# crowlar.net
KiCad netlist of a schematic drawn in EAGLE
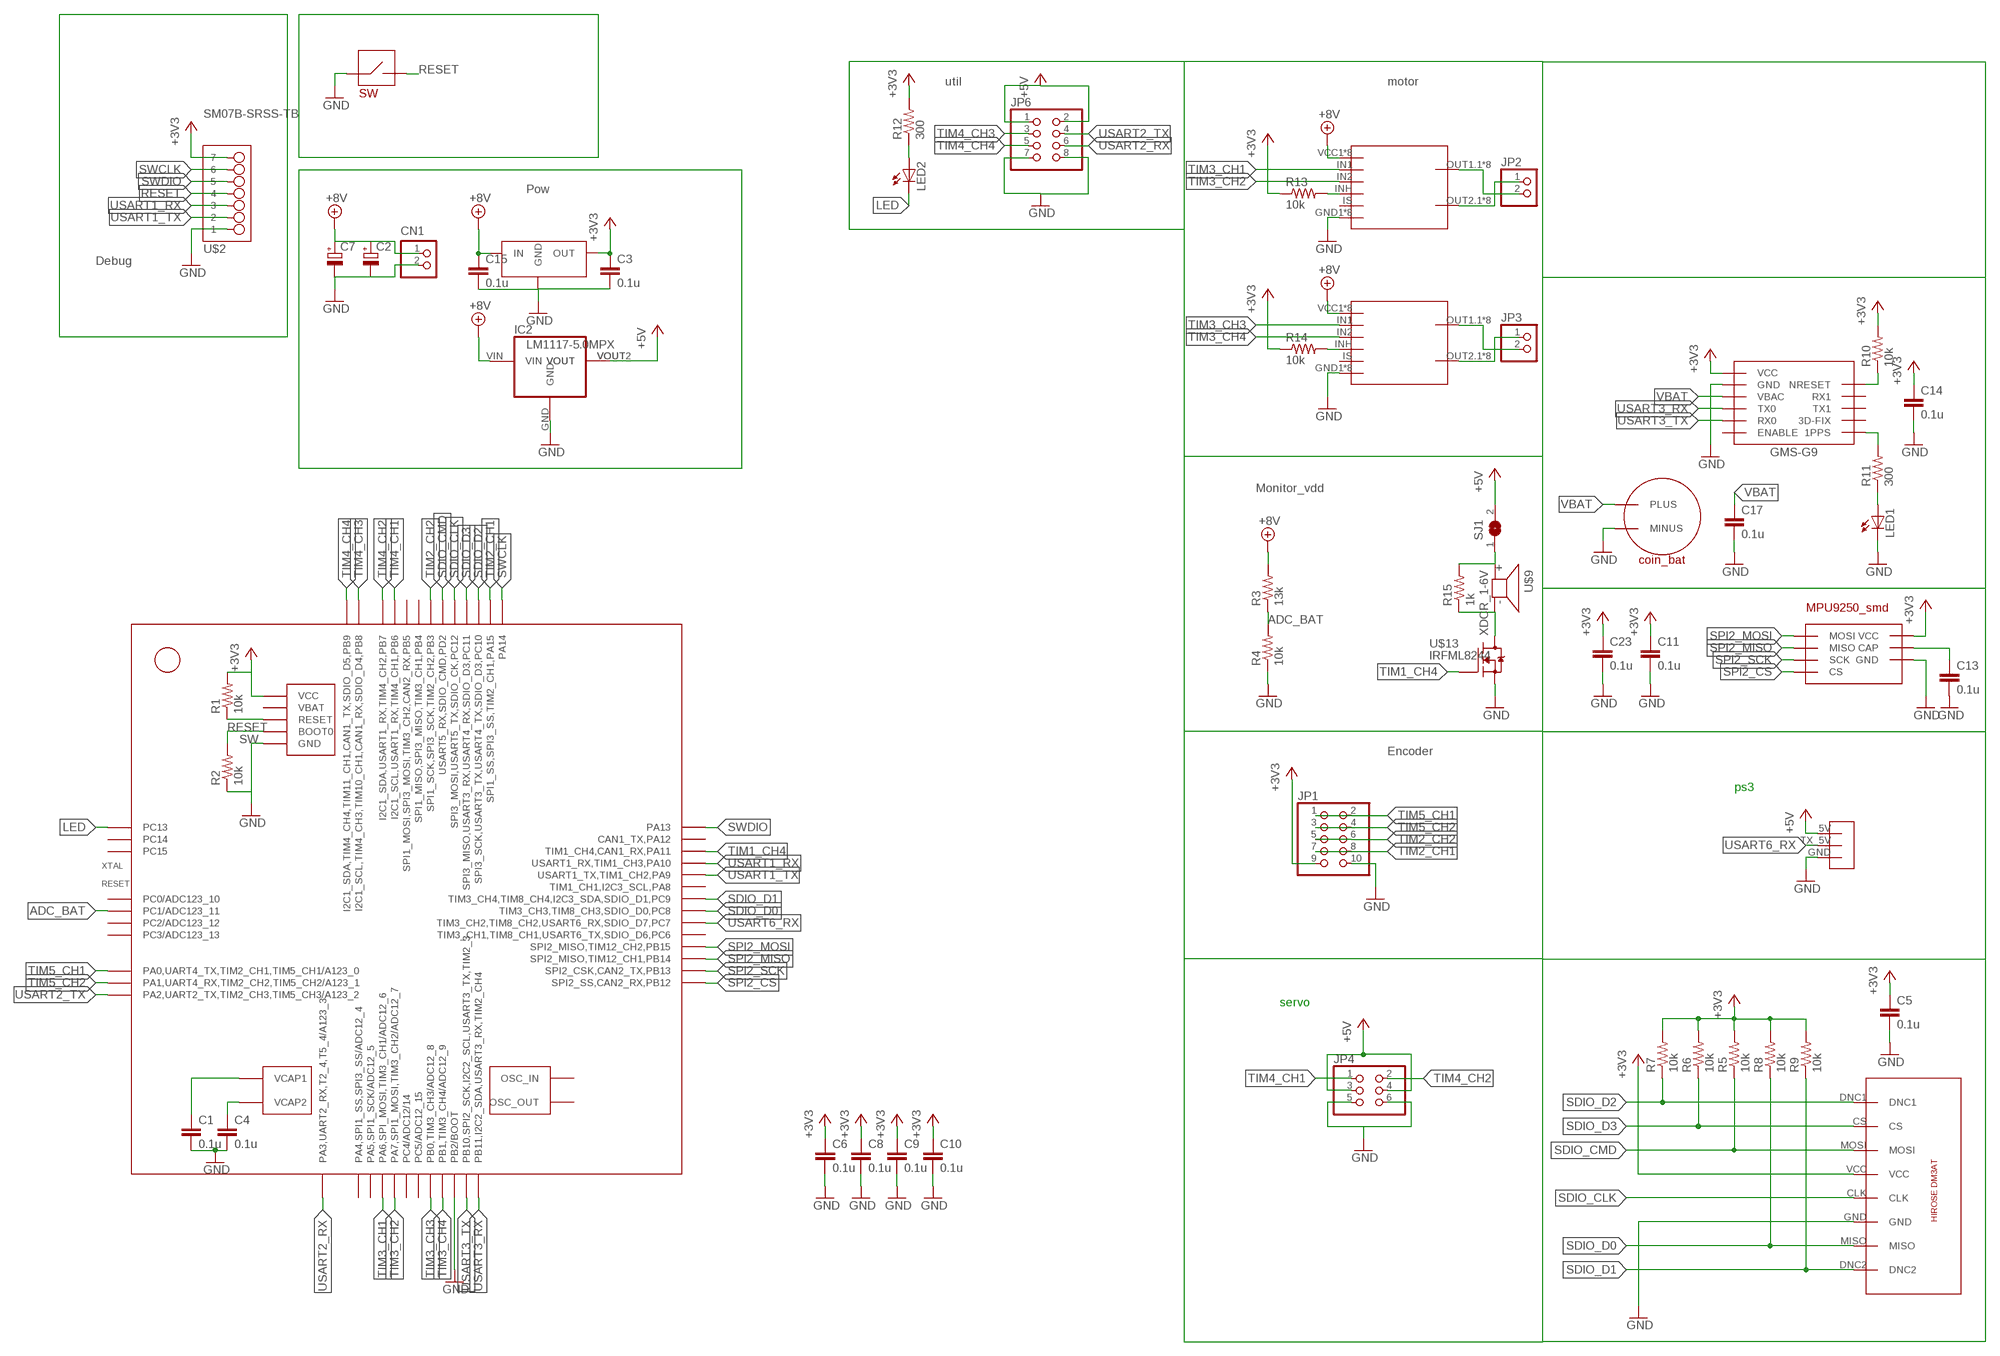
[diagram p0: schematic, sheet 1]

(export (version "E")
  (design (tool "Eeschema 10.0.6"))
  (components
    (comp (ref "C1")
      (value "0.1u")
      (footprint "eagle-import:C0603K")
      (libsource (lib "eagle-import") (part "C-EUC0603K"))
    )
    (comp (ref "C2")
      (value "CPOL-EU153CLV-0605")
      (footprint "eagle-import:153CLV-0605")
      (libsource (lib "eagle-import") (part "CPOL-EU153CLV-0605"))
    )
    (comp (ref "C3")
      (value "0.1u")
      (footprint "eagle-import:C0603K")
      (libsource (lib "eagle-import") (part "C-EUC0603K"))
    )
    (comp (ref "C4")
      (value "0.1u")
      (footprint "eagle-import:C0603K")
      (libsource (lib "eagle-import") (part "C-EUC0603K"))
    )
    (comp (ref "C5")
      (value "0.1u")
      (footprint "eagle-import:C0603K")
      (libsource (lib "eagle-import") (part "C-EUC0603K"))
    )
    (comp (ref "C6")
      (value "0.1u")
      (footprint "eagle-import:C0603K")
      (libsource (lib "eagle-import") (part "C-EUC0603K"))
    )
    (comp (ref "C7")
      (value "CPOL-EU153CLV-0605")
      (footprint "eagle-import:153CLV-0605")
      (libsource (lib "eagle-import") (part "CPOL-EU153CLV-0605"))
    )
    (comp (ref "C8")
      (value "0.1u")
      (footprint "eagle-import:C0603K")
      (libsource (lib "eagle-import") (part "C-EUC0603K"))
    )
    (comp (ref "C9")
      (value "0.1u")
      (footprint "eagle-import:C0603K")
      (libsource (lib "eagle-import") (part "C-EUC0603K"))
    )
    (comp (ref "C10")
      (value "0.1u")
      (footprint "eagle-import:C0603K")
      (libsource (lib "eagle-import") (part "C-EUC0603K"))
    )
    (comp (ref "C11")
      (value "0.1u")
      (footprint "eagle-import:C0603K")
      (libsource (lib "eagle-import") (part "C-EUC0603K"))
    )
    (comp (ref "C13")
      (value "0.1u")
      (footprint "eagle-import:C0603K")
      (libsource (lib "eagle-import") (part "C-EUC0603K"))
    )
    (comp (ref "C14")
      (value "0.1u")
      (footprint "eagle-import:C0603K")
      (libsource (lib "eagle-import") (part "C-EUC0603K"))
    )
    (comp (ref "C15")
      (value "0.1u")
      (footprint "eagle-import:C0603K")
      (libsource (lib "eagle-import") (part "C-EUC0603K"))
    )
    (comp (ref "C17")
      (value "0.1u")
      (footprint "eagle-import:C0603K")
      (libsource (lib "eagle-import") (part "C-EUC0603K"))
    )
    (comp (ref "C23")
      (value "0.1u")
      (footprint "eagle-import:C0603K")
      (libsource (lib "eagle-import") (part "C-EUC0603K"))
    )
    (comp (ref "CN1")
      (value "S2B-XASK-1")
      (footprint "eagle-import:S2B-XASK-1")
      (libsource (lib "eagle-import") (part "S2B-XASK-1"))
    )
    (comp (ref "IC2")
      (value "LM1117-5.0MPX")
      (footprint "eagle-import:SOT223")
      (libsource (lib "eagle-import") (part "LM1117IMP-5.0"))
    )
    (comp (ref "JP1")
      (value "PINHD-2X5/90")
      (footprint "eagle-import:2X05_90")
      (libsource (lib "eagle-import") (part "PINHD-2X5/90"))
    )
    (comp (ref "JP2")
      (value "PINHD-1X2/90")
      (footprint "eagle-import:1X02_90")
      (libsource (lib "eagle-import") (part "PINHD-1X2/90"))
    )
    (comp (ref "JP3")
      (value "PINHD-1X2/90")
      (footprint "eagle-import:1X02_90")
      (libsource (lib "eagle-import") (part "PINHD-1X2/90"))
    )
    (comp (ref "JP4")
      (value "PINHD-2X3/90")
      (footprint "eagle-import:2X03_90")
      (libsource (lib "eagle-import") (part "PINHD-2X3/90"))
    )
    (comp (ref "JP6")
      (value "PINHD-2X4/90")
      (footprint "eagle-import:2X04_90")
      (libsource (lib "eagle-import") (part "PINHD-2X4/90"))
    )
    (comp (ref "LED1")
      (value "LEDCHIP-LED0603")
      (footprint "eagle-import:CHIP-LED0603")
      (libsource (lib "eagle-import") (part "LEDCHIP-LED0603"))
    )
    (comp (ref "LED2")
      (value "LEDCHIP-LED0603")
      (footprint "eagle-import:CHIP-LED0603")
      (libsource (lib "eagle-import") (part "LEDCHIP-LED0603"))
    )
    (comp (ref "R1")
      (value "10k")
      (footprint "eagle-import:R0603")
      (libsource (lib "eagle-import") (part "R-US_R0603"))
    )
    (comp (ref "R2")
      (value "10k")
      (footprint "eagle-import:R0603")
      (libsource (lib "eagle-import") (part "R-US_R0603"))
    )
    (comp (ref "R3")
      (value "13k")
      (footprint "eagle-import:R0603")
      (libsource (lib "eagle-import") (part "R-US_R0603"))
    )
    (comp (ref "R4")
      (value "10k")
      (footprint "eagle-import:R0603")
      (libsource (lib "eagle-import") (part "R-US_R0603"))
    )
    (comp (ref "R5")
      (value "10k")
      (footprint "eagle-import:R0603")
      (libsource (lib "eagle-import") (part "R-US_R0603"))
    )
    (comp (ref "R6")
      (value "10k")
      (footprint "eagle-import:R0603")
      (libsource (lib "eagle-import") (part "R-US_R0603"))
    )
    (comp (ref "R7")
      (value "10k")
      (footprint "eagle-import:R0603")
      (libsource (lib "eagle-import") (part "R-US_R0603"))
    )
    (comp (ref "R8")
      (value "10k")
      (footprint "eagle-import:R0603")
      (libsource (lib "eagle-import") (part "R-US_R0603"))
    )
    (comp (ref "R9")
      (value "10k")
      (footprint "eagle-import:R0603")
      (libsource (lib "eagle-import") (part "R-US_R0603"))
    )
    (comp (ref "R10")
      (value "10k")
      (footprint "eagle-import:R0603")
      (libsource (lib "eagle-import") (part "R-US_R0603"))
    )
    (comp (ref "R11")
      (value "300")
      (footprint "eagle-import:R0603")
      (libsource (lib "eagle-import") (part "R-US_R0603"))
    )
    (comp (ref "R12")
      (value "300")
      (footprint "eagle-import:R0603")
      (libsource (lib "eagle-import") (part "R-US_R0603"))
    )
    (comp (ref "R13")
      (value "10k")
      (footprint "eagle-import:R0603")
      (libsource (lib "eagle-import") (part "R-US_R0603"))
    )
    (comp (ref "R14")
      (value "10k")
      (footprint "eagle-import:R0603")
      (libsource (lib "eagle-import") (part "R-US_R0603"))
    )
    (comp (ref "R15")
      (value "1k")
      (footprint "eagle-import:R0603")
      (libsource (lib "eagle-import") (part "R-US_R0603"))
    )
    (comp (ref "SJ1") (value "SJ") (footprint "eagle-import:SJ") (libsource (lib "eagle-import") (part "SJ")))
    (comp (ref "STM32F405RGT6")
      (value "STM32F405_T")
      (footprint "eagle-import:LQFP64")
      (libsource (lib "eagle-import") (part "STM32F405_T"))
    )
    (comp (ref "U$1")
      (value "GMS-G9")
      (footprint "eagle-import:GMS-G9")
      (libsource (lib "eagle-import") (part "GMS-G9"))
    )
    (comp (ref "U$2")
      (value "SM07B-SRSS-TB")
      (footprint "eagle-import:SM07B-SRSS-TB")
      (libsource (lib "eagle-import") (part "SM07B-SRSS-TB"))
    )
    (comp (ref "U$3")
      (value "SBDBT_5V")
      (footprint "eagle-import:SBDBT_5V")
      (libsource (lib "eagle-import") (part "SBDBT_5V"))
    )
    (comp (ref "U$4")
      (value "BTM7752")
      (footprint "eagle-import:BTM7752")
      (libsource (lib "eagle-import") (part "BTM7752"))
    )
    (comp (ref "U$5")
      (value "DM3AT")
      (footprint "eagle-import:DM3AT")
      (libsource (lib "eagle-import") (part "DM3AT"))
    )
    (comp (ref "U$6")
      (value "SWTVBP06-B043CB-B")
      (footprint "eagle-import:SW")
      (libsource (lib "eagle-import") (part "SWTVBP06-B043CB-B"))
    )
    (comp (ref "U$8")
      (value "AP7361-33E")
      (footprint "eagle-import:SOT223")
      (libsource (lib "eagle-import") (part "AP7361-33E"))
    )
    (comp (ref "U$9")
      (value "XDCR_1-6V")
      (footprint "eagle-import:XDCR_1-6V")
      (libsource (lib "eagle-import") (part "XDCR_1-6V"))
    )
    (comp (ref "U$10")
      (value "36-3030-ND")
      (footprint "eagle-import:36-3030-ND")
      (libsource (lib "eagle-import") (part "36-3030-ND"))
    )
    (comp (ref "U$11")
      (value "BTM7752")
      (footprint "eagle-import:BTM7752")
      (libsource (lib "eagle-import") (part "BTM7752"))
    )
    (comp (ref "U$13")
      (value "IRFML8244")
      (footprint "eagle-import:SOT23")
      (libsource (lib "eagle-import") (part "IRFML8244"))
    )
    (comp (ref "U$16")
      (value "MPU9250_SMD")
      (footprint "eagle-import:MPU9250_SMD")
      (libsource (lib "eagle-import") (part "MPU9250_SMD"))
    )
  )
  (nets
    (net (code "1") (name "+3V3") (class "Default")
      (node (ref "C10") (pin "1") (pinfunction "1_1") (pintype "passive"))
      (node (ref "C11") (pin "1") (pinfunction "1_1") (pintype "passive"))
      (node (ref "C14") (pin "1") (pinfunction "1_1") (pintype "passive"))
      (node (ref "C23") (pin "1") (pinfunction "1_1") (pintype "passive"))
      (node (ref "C3") (pin "1") (pinfunction "1_1") (pintype "passive"))
      (node (ref "C5") (pin "1") (pinfunction "1_1") (pintype "passive"))
      (node (ref "C6") (pin "1") (pinfunction "1_1") (pintype "passive"))
      (node (ref "C8") (pin "1") (pinfunction "1_1") (pintype "passive"))
      (node (ref "C9") (pin "1") (pinfunction "1_1") (pintype "passive"))
      (node (ref "JP1") (pin "9") (pinfunction "9_9") (pintype "passive"))
      (node (ref "R1") (pin "2") (pinfunction "2_2") (pintype "passive"))
      (node (ref "R10") (pin "2") (pinfunction "2_2") (pintype "passive"))
      (node (ref "R12") (pin "2") (pinfunction "2_2") (pintype "passive"))
      (node (ref "R13") (pin "1") (pinfunction "1_1") (pintype "passive"))
      (node (ref "R14") (pin "1") (pinfunction "1_1") (pintype "passive"))
      (node (ref "R5") (pin "2") (pinfunction "2_2") (pintype "passive"))
      (node (ref "R6") (pin "2") (pinfunction "2_2") (pintype "passive"))
      (node (ref "R7") (pin "2") (pinfunction "2_2") (pintype "passive"))
      (node (ref "R8") (pin "2") (pinfunction "2_2") (pintype "passive"))
      (node (ref "R9") (pin "2") (pinfunction "2_2") (pintype "passive"))
      (node (ref "STM32F405RGT6") (pin "13") (pinfunction "VCC_13") (pintype "bidirectional"))
      (node (ref "STM32F405RGT6") (pin "19") (pinfunction "VCC_19") (pintype "bidirectional"))
      (node (ref "STM32F405RGT6") (pin "32") (pinfunction "VCC_32") (pintype "bidirectional"))
      (node (ref "STM32F405RGT6") (pin "48") (pinfunction "VCC_48") (pintype "bidirectional"))
      (node (ref "STM32F405RGT6") (pin "64") (pinfunction "VCC_64") (pintype "bidirectional"))
      (node (ref "U$1") (pin "VCC") (pinfunction "VCC_VCC") (pintype "bidirectional"))
      (node (ref "U$16") (pin "RESV") (pinfunction "VCC_RESV") (pintype "bidirectional"))
      (node (ref "U$16") (pin "VDD") (pinfunction "VCC_VDD") (pintype "bidirectional"))
      (node (ref "U$16") (pin "VDDIO") (pinfunction "VCC_VDDIO") (pintype "bidirectional"))
      (node (ref "U$2") (pin "P$7") (pinfunction "7_P$7") (pintype "bidirectional"))
      (node (ref "U$5") (pin "VCC") (pinfunction "VCC_VCC") (pintype "bidirectional"))
      (node (ref "U$8") (pin "OUT") (pinfunction "OUT_OUT") (pintype "bidirectional"))
    )
    (net (code "2") (name "+5V") (class "Default")
      (node (ref "IC2") (pin "VOUT") (pinfunction "VOUT_VOUT") (pintype "output"))
      (node (ref "IC2") (pin "VOUT2") (pinfunction "VOUT_VOUT2") (pintype "output"))
      (node (ref "JP4") (pin "3") (pinfunction "3_3") (pintype "passive"))
      (node (ref "JP4") (pin "4") (pinfunction "4_4") (pintype "passive"))
      (node (ref "JP6") (pin "1") (pinfunction "1_1") (pintype "passive"))
      (node (ref "JP6") (pin "2") (pinfunction "2_2") (pintype "passive"))
      (node (ref "SJ1") (pin "2") (pinfunction "2_2") (pintype "passive"))
      (node (ref "U$3") (pin "5V") (pinfunction "5V_5V") (pintype "bidirectional"))
    )
    (net (code "3") (name "+8V") (class "Default")
      (node (ref "C15") (pin "1") (pinfunction "1_1") (pintype "passive"))
      (node (ref "C2") (pin "+") (pinfunction "+_+") (pintype "passive"))
      (node (ref "C7") (pin "+") (pinfunction "+_+") (pintype "passive"))
      (node (ref "CN1") (pin "1") (pinfunction "1_1") (pintype "passive"))
      (node (ref "IC2") (pin "VIN") (pinfunction "VIN_VIN") (pintype "input"))
      (node (ref "R3") (pin "2") (pinfunction "2_2") (pintype "passive"))
      (node (ref "U$11") (pin "VCC1") (pinfunction "VCC_VCC1") (pintype "bidirectional"))
      (node (ref "U$11") (pin "VCC2") (pinfunction "VCC_VCC2") (pintype "bidirectional"))
      (node (ref "U$11") (pin "VCC3") (pinfunction "VCC_VCC3") (pintype "bidirectional"))
      (node (ref "U$11") (pin "VCC4") (pinfunction "VCC_VCC4") (pintype "bidirectional"))
      (node (ref "U$11") (pin "VCC5") (pinfunction "VCC_VCC5") (pintype "bidirectional"))
      (node (ref "U$11") (pin "VCC6") (pinfunction "VCC_VCC6") (pintype "bidirectional"))
      (node (ref "U$11") (pin "VCC7") (pinfunction "VCC_VCC7") (pintype "bidirectional"))
      (node (ref "U$11") (pin "VCC8") (pinfunction "VCC_VCC8") (pintype "bidirectional"))
      (node (ref "U$4") (pin "VCC1") (pinfunction "VCC_VCC1") (pintype "bidirectional"))
      (node (ref "U$4") (pin "VCC2") (pinfunction "VCC_VCC2") (pintype "bidirectional"))
      (node (ref "U$4") (pin "VCC3") (pinfunction "VCC_VCC3") (pintype "bidirectional"))
      (node (ref "U$4") (pin "VCC4") (pinfunction "VCC_VCC4") (pintype "bidirectional"))
      (node (ref "U$4") (pin "VCC5") (pinfunction "VCC_VCC5") (pintype "bidirectional"))
      (node (ref "U$4") (pin "VCC6") (pinfunction "VCC_VCC6") (pintype "bidirectional"))
      (node (ref "U$4") (pin "VCC7") (pinfunction "VCC_VCC7") (pintype "bidirectional"))
      (node (ref "U$4") (pin "VCC8") (pinfunction "VCC_VCC8") (pintype "bidirectional"))
      (node (ref "U$8") (pin "IN") (pinfunction "IN_IN") (pintype "bidirectional"))
    )
    (net (code "4") (name "/SW") (class "Default")
      (node (ref "R2") (pin "2") (pinfunction "2_2") (pintype "passive"))
      (node (ref "STM32F405RGT6") (pin "60") (pinfunction "BOOT0_60") (pintype "bidirectional"))
    )
    (net (code "5") (name "ADC_BAT") (class "Default")
      (node (ref "R3") (pin "1") (pinfunction "1_1") (pintype "passive"))
      (node (ref "R4") (pin "2") (pinfunction "2_2") (pintype "passive"))
      (node (ref "STM32F405RGT6") (pin "9") (pinfunction "PC1/ADC123_11_9") (pintype "bidirectional"))
    )
    (net (code "6") (name "GND") (class "Default")
      (node (ref "C1") (pin "2") (pinfunction "2_2") (pintype "passive"))
      (node (ref "C10") (pin "2") (pinfunction "2_2") (pintype "passive"))
      (node (ref "C11") (pin "2") (pinfunction "2_2") (pintype "passive"))
      (node (ref "C13") (pin "2") (pinfunction "2_2") (pintype "passive"))
      (node (ref "C14") (pin "2") (pinfunction "2_2") (pintype "passive"))
      (node (ref "C15") (pin "2") (pinfunction "2_2") (pintype "passive"))
      (node (ref "C17") (pin "2") (pinfunction "2_2") (pintype "passive"))
      (node (ref "C2") (pin "-") (pinfunction "-_-") (pintype "passive"))
      (node (ref "C23") (pin "2") (pinfunction "2_2") (pintype "passive"))
      (node (ref "C3") (pin "2") (pinfunction "2_2") (pintype "passive"))
      (node (ref "C4") (pin "2") (pinfunction "2_2") (pintype "passive"))
      (node (ref "C5") (pin "2") (pinfunction "2_2") (pintype "passive"))
      (node (ref "C6") (pin "2") (pinfunction "2_2") (pintype "passive"))
      (node (ref "C7") (pin "-") (pinfunction "-_-") (pintype "passive"))
      (node (ref "C8") (pin "2") (pinfunction "2_2") (pintype "passive"))
      (node (ref "C9") (pin "2") (pinfunction "2_2") (pintype "passive"))
      (node (ref "CN1") (pin "2") (pinfunction "2_2") (pintype "passive"))
      (node (ref "IC2") (pin "GND") (pinfunction "GND_GND") (pintype "power_in"))
      (node (ref "JP1") (pin "10") (pinfunction "10_10") (pintype "passive"))
      (node (ref "JP4") (pin "5") (pinfunction "5_5") (pintype "passive"))
      (node (ref "JP4") (pin "6") (pinfunction "6_6") (pintype "passive"))
      (node (ref "JP6") (pin "7") (pinfunction "7_7") (pintype "passive"))
      (node (ref "JP6") (pin "8") (pinfunction "8_8") (pintype "passive"))
      (node (ref "LED1") (pin "C") (pinfunction "C_C") (pintype "passive"))
      (node (ref "R2") (pin "1") (pinfunction "1_1") (pintype "passive"))
      (node (ref "R4") (pin "1") (pinfunction "1_1") (pintype "passive"))
      (node (ref "STM32F405RGT6") (pin "12") (pinfunction "GND_12") (pintype "bidirectional"))
      (node (ref "STM32F405RGT6") (pin "18") (pinfunction "GND_18") (pintype "bidirectional"))
      (node (ref "STM32F405RGT6") (pin "28") (pinfunction "PB2/BOOT_28") (pintype "bidirectional"))
      (node (ref "STM32F405RGT6") (pin "63") (pinfunction "GND_63") (pintype "bidirectional"))
      (node (ref "U$1") (pin "GND") (pinfunction "GND_GND") (pintype "bidirectional"))
      (node (ref "U$1") (pin "GND1") (pinfunction "GND_GND1") (pintype "bidirectional"))
      (node (ref "U$10") (pin "MINUS") (pinfunction "MINUS_MINUS") (pintype "bidirectional"))
      (node (ref "U$11") (pin "GND1") (pinfunction "GND_GND1") (pintype "bidirectional"))
      (node (ref "U$11") (pin "GND2") (pinfunction "GND_GND2") (pintype "bidirectional"))
      (node (ref "U$11") (pin "GND3") (pinfunction "GND_GND3") (pintype "bidirectional"))
      (node (ref "U$11") (pin "GND4") (pinfunction "GND_GND4") (pintype "bidirectional"))
      (node (ref "U$11") (pin "GND5") (pinfunction "GND_GND5") (pintype "bidirectional"))
      (node (ref "U$11") (pin "GND6") (pinfunction "GND_GND6") (pintype "bidirectional"))
      (node (ref "U$11") (pin "GND7") (pinfunction "GND_GND7") (pintype "bidirectional"))
      (node (ref "U$11") (pin "GND8") (pinfunction "GND_GND8") (pintype "bidirectional"))
      (node (ref "U$13") (pin "2") (pinfunction "S_2") (pintype "passive"))
      (node (ref "U$16") (pin "GND") (pinfunction "GND_GND") (pintype "bidirectional"))
      (node (ref "U$16") (pin "~RESV") (pinfunction "GND_~RESV") (pintype "bidirectional"))
      (node (ref "U$2") (pin "P$1") (pinfunction "1_P$1") (pintype "bidirectional"))
      (node (ref "U$3") (pin "GND") (pinfunction "GND_GND") (pintype "bidirectional"))
      (node (ref "U$4") (pin "GND1") (pinfunction "GND_GND1") (pintype "bidirectional"))
      (node (ref "U$4") (pin "GND2") (pinfunction "GND_GND2") (pintype "bidirectional"))
      (node (ref "U$4") (pin "GND3") (pinfunction "GND_GND3") (pintype "bidirectional"))
      (node (ref "U$4") (pin "GND4") (pinfunction "GND_GND4") (pintype "bidirectional"))
      (node (ref "U$4") (pin "GND5") (pinfunction "GND_GND5") (pintype "bidirectional"))
      (node (ref "U$4") (pin "GND6") (pinfunction "GND_GND6") (pintype "bidirectional"))
      (node (ref "U$4") (pin "GND7") (pinfunction "GND_GND7") (pintype "bidirectional"))
      (node (ref "U$4") (pin "GND8") (pinfunction "GND_GND8") (pintype "bidirectional"))
      (node (ref "U$5") (pin "GND") (pinfunction "GND_GND") (pintype "bidirectional"))
      (node (ref "U$6") (pin "P$1") (pinfunction "P$1_P$1") (pintype "bidirectional"))
      (node (ref "U$8") (pin "GND1") (pinfunction "GND_GND1") (pintype "bidirectional"))
      (node (ref "U$8") (pin "GND2") (pinfunction "GND_GND2") (pintype "bidirectional"))
    )
    (net (code "7") (name "LED") (class "Default")
      (node (ref "LED2") (pin "C") (pinfunction "C_C") (pintype "passive"))
      (node (ref "STM32F405RGT6") (pin "2") (pinfunction "PC13_2") (pintype "bidirectional"))
    )
    (net (code "8") (name "Net-(JP2-Pad1)") (class "Default")
      (node (ref "JP2") (pin "1") (pinfunction "1_1") (pintype "passive"))
      (node (ref "U$4") (pin "OUT2.1") (pinfunction "OUT2_OUT2.1") (pintype "bidirectional"))
      (node (ref "U$4") (pin "OUT2.2") (pinfunction "OUT2_OUT2.2") (pintype "bidirectional"))
      (node (ref "U$4") (pin "OUT2.3") (pinfunction "OUT2_OUT2.3") (pintype "bidirectional"))
      (node (ref "U$4") (pin "OUT2.4") (pinfunction "OUT2_OUT2.4") (pintype "bidirectional"))
      (node (ref "U$4") (pin "OUT2.5") (pinfunction "OUT2_OUT2.5") (pintype "bidirectional"))
      (node (ref "U$4") (pin "OUT2.6") (pinfunction "OUT2_OUT2.6") (pintype "bidirectional"))
      (node (ref "U$4") (pin "OUT2.7") (pinfunction "OUT2_OUT2.7") (pintype "bidirectional"))
      (node (ref "U$4") (pin "OUT2.8") (pinfunction "OUT2_OUT2.8") (pintype "bidirectional"))
    )
    (net (code "9") (name "Net-(JP2-Pad2)") (class "Default")
      (node (ref "JP2") (pin "2") (pinfunction "2_2") (pintype "passive"))
      (node (ref "U$4") (pin "OUT1.1") (pinfunction "OUT1_OUT1.1") (pintype "bidirectional"))
      (node (ref "U$4") (pin "OUT1.2") (pinfunction "OUT1_OUT1.2") (pintype "bidirectional"))
      (node (ref "U$4") (pin "OUT1.3") (pinfunction "OUT1_OUT1.3") (pintype "bidirectional"))
      (node (ref "U$4") (pin "OUT1.4") (pinfunction "OUT1_OUT1.4") (pintype "bidirectional"))
      (node (ref "U$4") (pin "OUT1.5") (pinfunction "OUT1_OUT1.5") (pintype "bidirectional"))
      (node (ref "U$4") (pin "OUT1.6") (pinfunction "OUT1_OUT1.6") (pintype "bidirectional"))
      (node (ref "U$4") (pin "OUT1.7") (pinfunction "OUT1_OUT1.7") (pintype "bidirectional"))
      (node (ref "U$4") (pin "OUT1.8") (pinfunction "OUT1_OUT1.8") (pintype "bidirectional"))
    )
    (net (code "10") (name "Net-(JP3-Pad1)") (class "Default")
      (node (ref "JP3") (pin "1") (pinfunction "1_1") (pintype "passive"))
      (node (ref "U$11") (pin "OUT2.1") (pinfunction "OUT2_OUT2.1") (pintype "bidirectional"))
      (node (ref "U$11") (pin "OUT2.2") (pinfunction "OUT2_OUT2.2") (pintype "bidirectional"))
      (node (ref "U$11") (pin "OUT2.3") (pinfunction "OUT2_OUT2.3") (pintype "bidirectional"))
      (node (ref "U$11") (pin "OUT2.4") (pinfunction "OUT2_OUT2.4") (pintype "bidirectional"))
      (node (ref "U$11") (pin "OUT2.5") (pinfunction "OUT2_OUT2.5") (pintype "bidirectional"))
      (node (ref "U$11") (pin "OUT2.6") (pinfunction "OUT2_OUT2.6") (pintype "bidirectional"))
      (node (ref "U$11") (pin "OUT2.7") (pinfunction "OUT2_OUT2.7") (pintype "bidirectional"))
      (node (ref "U$11") (pin "OUT2.8") (pinfunction "OUT2_OUT2.8") (pintype "bidirectional"))
    )
    (net (code "11") (name "Net-(JP3-Pad2)") (class "Default")
      (node (ref "JP3") (pin "2") (pinfunction "2_2") (pintype "passive"))
      (node (ref "U$11") (pin "OUT1.1") (pinfunction "OUT1_OUT1.1") (pintype "bidirectional"))
      (node (ref "U$11") (pin "OUT1.2") (pinfunction "OUT1_OUT1.2") (pintype "bidirectional"))
      (node (ref "U$11") (pin "OUT1.3") (pinfunction "OUT1_OUT1.3") (pintype "bidirectional"))
      (node (ref "U$11") (pin "OUT1.4") (pinfunction "OUT1_OUT1.4") (pintype "bidirectional"))
      (node (ref "U$11") (pin "OUT1.5") (pinfunction "OUT1_OUT1.5") (pintype "bidirectional"))
      (node (ref "U$11") (pin "OUT1.6") (pinfunction "OUT1_OUT1.6") (pintype "bidirectional"))
      (node (ref "U$11") (pin "OUT1.7") (pinfunction "OUT1_OUT1.7") (pintype "bidirectional"))
      (node (ref "U$11") (pin "OUT1.8") (pinfunction "OUT1_OUT1.8") (pintype "bidirectional"))
    )
    (net (code "12") (name "Net-(LED1-PadA)") (class "Default")
      (node (ref "LED1") (pin "A") (pinfunction "A_A") (pintype "passive"))
      (node (ref "R11") (pin "1") (pinfunction "1_1") (pintype "passive"))
    )
    (net (code "13") (name "Net-(LED2-PadA)") (class "Default")
      (node (ref "LED2") (pin "A") (pinfunction "A_A") (pintype "passive"))
      (node (ref "R12") (pin "1") (pinfunction "1_1") (pintype "passive"))
    )
    (net (code "14") (name "Net-(R10-Pad1)") (class "Default")
      (node (ref "R10") (pin "1") (pinfunction "1_1") (pintype "passive"))
      (node (ref "U$1") (pin "NRESET") (pinfunction "NRESET_NRESET") (pintype "bidirectional"))
    )
    (net (code "15") (name "Net-(R11-Pad2)") (class "Default")
      (node (ref "R11") (pin "2") (pinfunction "2_2") (pintype "passive"))
      (node (ref "U$1") (pin "1PPS") (pinfunction "1PPS_1PPS") (pintype "bidirectional"))
    )
    (net (code "16") (name "Net-(R13-Pad2)") (class "Default")
      (node (ref "R13") (pin "2") (pinfunction "2_2") (pintype "passive"))
      (node (ref "U$4") (pin "INH") (pinfunction "INH_INH") (pintype "bidirectional"))
    )
    (net (code "17") (name "Net-(R14-Pad2)") (class "Default")
      (node (ref "R14") (pin "2") (pinfunction "2_2") (pintype "passive"))
      (node (ref "U$11") (pin "INH") (pinfunction "INH_INH") (pintype "bidirectional"))
    )
    (net (code "18") (name "Net-(R15-Pad2)") (class "Default")
      (node (ref "R15") (pin "2") (pinfunction "2_2") (pintype "passive"))
      (node (ref "SJ1") (pin "1") (pinfunction "1_1") (pintype "passive"))
      (node (ref "U$9") (pin "PLUS") (pinfunction "PLUS_PLUS") (pintype "passive"))
    )
    (net (code "19") (name "Net-(STM32F405RGT6-VCAP1)") (class "Default")
      (node (ref "C1") (pin "1") (pinfunction "1_1") (pintype "passive"))
      (node (ref "STM32F405RGT6") (pin "31") (pinfunction "VCAP1_31") (pintype "bidirectional"))
    )
    (net (code "20") (name "Net-(STM32F405RGT6-VCAP2)") (class "Default")
      (node (ref "C4") (pin "1") (pinfunction "1_1") (pintype "passive"))
      (node (ref "STM32F405RGT6") (pin "47") (pinfunction "VCAP2_47") (pintype "bidirectional"))
    )
    (net (code "21") (name "Net-(U$13-D)") (class "Default")
      (node (ref "R15") (pin "1") (pinfunction "1_1") (pintype "passive"))
      (node (ref "U$13") (pin "3") (pinfunction "D_3") (pintype "passive"))
      (node (ref "U$9") (pin "MINUS") (pinfunction "2_MINUS") (pintype "passive"))
    )
    (net (code "22") (name "Net-(U$16-CAP)") (class "Default")
      (node (ref "C13") (pin "1") (pinfunction "1_1") (pintype "passive"))
      (node (ref "U$16") (pin "REGOUT") (pinfunction "CAP_REGOUT") (pintype "bidirectional"))
    )
    (net (code "23") (name "RESET") (class "Default")
      (node (ref "R1") (pin "1") (pinfunction "1_1") (pintype "passive"))
      (node (ref "STM32F405RGT6") (pin "7") (pinfunction "RESET_7") (pintype "bidirectional"))
      (node (ref "U$2") (pin "P$4") (pinfunction "4_P$4") (pintype "bidirectional"))
      (node (ref "U$6") (pin "P$2") (pinfunction "P$2_P$2") (pintype "bidirectional"))
    )
    (net (code "24") (name "SDIO_CLK") (class "Default")
      (node (ref "STM32F405RGT6") (pin "53") (pinfunction "SPI3_MOSI,USART5_TX,SDIO_CK,PC12_53") (pintype "bidirectional"))
      (node (ref "U$5") (pin "CLK") (pinfunction "CLK_CLK") (pintype "bidirectional"))
    )
    (net (code "25") (name "SDIO_CMD") (class "Default")
      (node (ref "R5") (pin "1") (pinfunction "1_1") (pintype "passive"))
      (node (ref "STM32F405RGT6") (pin "54") (pinfunction "USART5_RX,SDIO_CMD,PD2_54") (pintype "bidirectional"))
      (node (ref "U$5") (pin "MOSI") (pinfunction "MOSI_MOSI") (pintype "bidirectional"))
    )
    (net (code "26") (name "SDIO_D0") (class "Default")
      (node (ref "R8") (pin "1") (pinfunction "1_1") (pintype "passive"))
      (node (ref "STM32F405RGT6") (pin "39") (pinfunction "TIM3_CH3,TIM8_CH3,SDIO_D0,PC8_39") (pintype "bidirectional"))
      (node (ref "U$5") (pin "MISO") (pinfunction "MISO_MISO") (pintype "bidirectional"))
    )
    (net (code "27") (name "SDIO_D1") (class "Default")
      (node (ref "R9") (pin "1") (pinfunction "1_1") (pintype "passive"))
      (node (ref "STM32F405RGT6") (pin "40") (pinfunction "TIM3_CH4,TIM8_CH4,I2C3_SDA,SDIO_D1,PC9_40") (pintype "bidirectional"))
      (node (ref "U$5") (pin "DNC2") (pinfunction "DNC2_DNC2") (pintype "bidirectional"))
    )
    (net (code "28") (name "SDIO_D2") (class "Default")
      (node (ref "R7") (pin "1") (pinfunction "1_1") (pintype "passive"))
      (node (ref "STM32F405RGT6") (pin "51") (pinfunction "SPI3_SCK,USART3_TX,USART4_TX,SDIO_D3,PC10_51") (pintype "bidirectional"))
      (node (ref "U$5") (pin "DNC1") (pinfunction "DNC1_DNC1") (pintype "bidirectional"))
    )
    (net (code "29") (name "SDIO_D3") (class "Default")
      (node (ref "R6") (pin "1") (pinfunction "1_1") (pintype "passive"))
      (node (ref "STM32F405RGT6") (pin "52") (pinfunction "SPI3_MISO,USART3_RX,USART4_RX,SDIO_D3,PC11_52") (pintype "bidirectional"))
      (node (ref "U$5") (pin "CS") (pinfunction "CS_CS") (pintype "bidirectional"))
    )
    (net (code "30") (name "SPI2_CS") (class "Default")
      (node (ref "STM32F405RGT6") (pin "33") (pinfunction "SPI2_SS,CAN2_RX,PB12_33") (pintype "bidirectional"))
      (node (ref "U$16") (pin "CS") (pinfunction "CS_CS") (pintype "bidirectional"))
    )
    (net (code "31") (name "SPI2_MISO") (class "Default")
      (node (ref "STM32F405RGT6") (pin "35") (pinfunction "SPI2_MISO,TIM12_CH1,PB14_35") (pintype "bidirectional"))
      (node (ref "U$16") (pin "MISO") (pinfunction "MISO_MISO") (pintype "bidirectional"))
    )
    (net (code "32") (name "SPI2_MOSI") (class "Default")
      (node (ref "STM32F405RGT6") (pin "36") (pinfunction "SPI2_MISO,TIM12_CH2,PB15_36") (pintype "bidirectional"))
      (node (ref "U$16") (pin "MOSI") (pinfunction "MOSI_MOSI") (pintype "bidirectional"))
    )
    (net (code "33") (name "SPI2_SCK") (class "Default")
      (node (ref "STM32F405RGT6") (pin "34") (pinfunction "SPI2_CSK,CAN2_TX,PB13_34") (pintype "bidirectional"))
      (node (ref "U$16") (pin "SCK") (pinfunction "SCK_SCK") (pintype "bidirectional"))
    )
    (net (code "34") (name "SWCLK") (class "Default")
      (node (ref "STM32F405RGT6") (pin "49") (pinfunction "PA14_49") (pintype "bidirectional"))
      (node (ref "U$2") (pin "P$6") (pinfunction "6_P$6") (pintype "bidirectional"))
    )
    (net (code "35") (name "SWDIO") (class "Default")
      (node (ref "STM32F405RGT6") (pin "46") (pinfunction "PA13_46") (pintype "bidirectional"))
      (node (ref "U$2") (pin "P$5") (pinfunction "5_P$5") (pintype "bidirectional"))
    )
    (net (code "36") (name "TIM1_CH4") (class "Default")
      (node (ref "STM32F405RGT6") (pin "44") (pinfunction "TIM1_CH4,CAN1_RX,PA11_44") (pintype "bidirectional"))
      (node (ref "U$13") (pin "1") (pinfunction "G_1") (pintype "passive"))
    )
    (net (code "37") (name "TIM2_CH1") (class "Default")
      (node (ref "JP1") (pin "7") (pinfunction "7_7") (pintype "passive"))
      (node (ref "JP1") (pin "8") (pinfunction "8_8") (pintype "passive"))
      (node (ref "STM32F405RGT6") (pin "50") (pinfunction "SPI1_SS,SPI3_SS,TIM2_CH1,PA15_50") (pintype "bidirectional"))
    )
    (net (code "38") (name "TIM2_CH2") (class "Default")
      (node (ref "JP1") (pin "5") (pinfunction "5_5") (pintype "passive"))
      (node (ref "JP1") (pin "6") (pinfunction "6_6") (pintype "passive"))
      (node (ref "STM32F405RGT6") (pin "55") (pinfunction "SPI1_SCK,SPI3_SCK,TIM2_CH2,PB3_55") (pintype "bidirectional"))
    )
    (net (code "39") (name "TIM3_CH1") (class "Default")
      (node (ref "STM32F405RGT6") (pin "22") (pinfunction "PA6,SPI_MOSI,TIM3_CH1/ADC12_6_22") (pintype "bidirectional"))
      (node (ref "U$4") (pin "IN1") (pinfunction "IN1_IN1") (pintype "bidirectional"))
    )
    (net (code "40") (name "TIM3_CH2") (class "Default")
      (node (ref "STM32F405RGT6") (pin "23") (pinfunction "PA7,SPI1_MOSI,TIM3_CH2/ADC12_7_23") (pintype "bidirectional"))
      (node (ref "U$4") (pin "IN2") (pinfunction "IN2_IN2") (pintype "bidirectional"))
    )
    (net (code "41") (name "TIM3_CH3") (class "Default")
      (node (ref "STM32F405RGT6") (pin "26") (pinfunction "PB0,TIM3_CH3/ADC12_8_26") (pintype "bidirectional"))
      (node (ref "U$11") (pin "IN1") (pinfunction "IN1_IN1") (pintype "bidirectional"))
    )
    (net (code "42") (name "TIM3_CH4") (class "Default")
      (node (ref "STM32F405RGT6") (pin "27") (pinfunction "PB1,TIM3_CH4/ADC12_9_27") (pintype "bidirectional"))
      (node (ref "U$11") (pin "IN2") (pinfunction "IN2_IN2") (pintype "bidirectional"))
    )
    (net (code "43") (name "TIM4_CH1") (class "Default")
      (node (ref "JP4") (pin "1") (pinfunction "1_1") (pintype "passive"))
      (node (ref "STM32F405RGT6") (pin "58") (pinfunction "I2C1_SCL,USART1_RX,TIM4_CH1,PB6_58") (pintype "bidirectional"))
    )
    (net (code "44") (name "TIM4_CH2") (class "Default")
      (node (ref "JP4") (pin "2") (pinfunction "2_2") (pintype "passive"))
      (node (ref "STM32F405RGT6") (pin "59") (pinfunction "I2C1_SDA,USART1_RX,TIM4_CH2,PB7_59") (pintype "bidirectional"))
    )
    (net (code "45") (name "TIM4_CH3") (class "Default")
      (node (ref "JP6") (pin "3") (pinfunction "3_3") (pintype "passive"))
      (node (ref "STM32F405RGT6") (pin "61") (pinfunction "I2C1_SCL,TIM4_CH3,TIM10_CH1,CAN1_RX,SDIO_D4,PB8_61") (pintype "bidirectional"))
    )
    (net (code "46") (name "TIM4_CH4") (class "Default")
      (node (ref "JP6") (pin "5") (pinfunction "5_5") (pintype "passive"))
      (node (ref "STM32F405RGT6") (pin "62") (pinfunction "I2C1_SDA,TIM4_CH4,TIM11_CH1,CAN1_TX,SDIO_D5,PB9_62") (pintype "bidirectional"))
    )
    (net (code "47") (name "TIM5_CH1") (class "Default")
      (node (ref "JP1") (pin "1") (pinfunction "1_1") (pintype "passive"))
      (node (ref "JP1") (pin "2") (pinfunction "2_2") (pintype "passive"))
      (node (ref "STM32F405RGT6") (pin "14") (pinfunction "PA0,UART4_TX,TIM2_CH1,TIM5_CH1/A123_0_14") (pintype "bidirectional"))
    )
    (net (code "48") (name "TIM5_CH2") (class "Default")
      (node (ref "JP1") (pin "3") (pinfunction "3_3") (pintype "passive"))
      (node (ref "JP1") (pin "4") (pinfunction "4_4") (pintype "passive"))
      (node (ref "STM32F405RGT6") (pin "15") (pinfunction "PA1,UART4_RX,TIM2_CH2,TIM5_CH2/A123_1_15") (pintype "bidirectional"))
    )
    (net (code "49") (name "USART1_RX") (class "Default")
      (node (ref "STM32F405RGT6") (pin "43") (pinfunction "USART1_RX,TIM1_CH3,PA10_43") (pintype "bidirectional"))
      (node (ref "U$2") (pin "P$3") (pinfunction "3_P$3") (pintype "bidirectional"))
    )
    (net (code "50") (name "USART1_TX") (class "Default")
      (node (ref "STM32F405RGT6") (pin "42") (pinfunction "USART1_TX,TIM1_CH2,PA9_42") (pintype "bidirectional"))
      (node (ref "U$2") (pin "P$2") (pinfunction "2_P$2") (pintype "bidirectional"))
    )
    (net (code "51") (name "USART2_RX") (class "Default")
      (node (ref "JP6") (pin "6") (pinfunction "6_6") (pintype "passive"))
      (node (ref "STM32F405RGT6") (pin "17") (pinfunction "PA3,UART2_RX,T2_4,T5_4/A123_3_17") (pintype "bidirectional"))
    )
    (net (code "52") (name "USART2_TX") (class "Default")
      (node (ref "JP6") (pin "4") (pinfunction "4_4") (pintype "passive"))
      (node (ref "STM32F405RGT6") (pin "16") (pinfunction "PA2,UART2_TX,TIM2_CH3,TIM5_CH3/A123_2_16") (pintype "bidirectional"))
    )
    (net (code "53") (name "USART3_RX") (class "Default")
      (node (ref "STM32F405RGT6") (pin "30") (pinfunction "PB11,I2C2_SDA,USART3_RX,TIM2_CH4_30") (pintype "bidirectional"))
      (node (ref "U$1") (pin "TX0") (pinfunction "TX0_TX0") (pintype "bidirectional"))
    )
    (net (code "54") (name "USART3_TX") (class "Default")
      (node (ref "STM32F405RGT6") (pin "29") (pinfunction "PB10,SPI2_SCK,I2C2_SCL,USART3_TX,TIM2_3_29") (pintype "bidirectional"))
      (node (ref "U$1") (pin "RX0") (pinfunction "RX0_RX0") (pintype "bidirectional"))
    )
    (net (code "55") (name "USART6_RX") (class "Default")
      (node (ref "STM32F405RGT6") (pin "38") (pinfunction "TIM3_CH2,TIM8_CH2,USART6_RX,SDIO_D7,PC7_38") (pintype "bidirectional"))
      (node (ref "U$3") (pin "TX_5V") (pinfunction "TX_5V_TX_5V") (pintype "bidirectional"))
    )
    (net (code "56") (name "VBAT") (class "Default")
      (node (ref "C17") (pin "1") (pinfunction "1_1") (pintype "passive"))
      (node (ref "U$1") (pin "VBAC") (pinfunction "VBAC_VBAC") (pintype "bidirectional"))
      (node (ref "U$10") (pin "PLUS1") (pinfunction "PLUS_PLUS1") (pintype "bidirectional"))
      (node (ref "U$10") (pin "PLUS2") (pinfunction "PLUS_PLUS2") (pintype "bidirectional"))
    )
    (net (code "57") (name "unconnected-(STM32F405RGT6-CAN1_TX,PA12-Pad45)") (class "Default")
      (node (ref "STM32F405RGT6") (pin "45") (pinfunction "CAN1_TX,PA12_45") (pintype "bidirectional"))
    )
    (net (code "58") (name "unconnected-(STM32F405RGT6-OSC_IN-Pad5)") (class "Default")
      (node (ref "STM32F405RGT6") (pin "5") (pinfunction "OSC_IN_5") (pintype "bidirectional"))
    )
    (net (code "59") (name "unconnected-(STM32F405RGT6-OSC_OUT-Pad6)") (class "Default")
      (node (ref "STM32F405RGT6") (pin "6") (pinfunction "OSC_OUT_6") (pintype "bidirectional"))
    )
    (net (code "60") (name "unconnected-(STM32F405RGT6-PA4,SPI1_SS,SPI3_SS{slash}ADC12_4-Pad20)") (class "Default")
      (node (ref "STM32F405RGT6") (pin "20") (pinfunction "PA4,SPI1_SS,SPI3_SS/ADC12_4_20") (pintype "bidirectional"))
    )
    (net (code "61") (name "unconnected-(STM32F405RGT6-PA5,SPI1_SCK{slash}ADC12_5-Pad21)") (class "Default")
      (node (ref "STM32F405RGT6") (pin "21") (pinfunction "PA5,SPI1_SCK/ADC12_5_21") (pintype "bidirectional"))
    )
    (net (code "62") (name "unconnected-(STM32F405RGT6-PC0{slash}ADC123_10-Pad8)") (class "Default")
      (node (ref "STM32F405RGT6") (pin "8") (pinfunction "PC0/ADC123_10_8") (pintype "bidirectional"))
    )
    (net (code "63") (name "unconnected-(STM32F405RGT6-PC2{slash}ADC123_12-Pad10)") (class "Default")
      (node (ref "STM32F405RGT6") (pin "10") (pinfunction "PC2/ADC123_12_10") (pintype "bidirectional"))
    )
    (net (code "64") (name "unconnected-(STM32F405RGT6-PC3{slash}ADC123_13-Pad11)") (class "Default")
      (node (ref "STM32F405RGT6") (pin "11") (pinfunction "PC3/ADC123_13_11") (pintype "bidirectional"))
    )
    (net (code "65") (name "unconnected-(STM32F405RGT6-PC4{slash}ADC12{slash}14-Pad24)") (class "Default")
      (node (ref "STM32F405RGT6") (pin "24") (pinfunction "PC4/ADC12/14_24") (pintype "bidirectional"))
    )
    (net (code "66") (name "unconnected-(STM32F405RGT6-PC5{slash}ADC12_15-Pad25)") (class "Default")
      (node (ref "STM32F405RGT6") (pin "25") (pinfunction "PC5/ADC12_15_25") (pintype "bidirectional"))
    )
    (net (code "67") (name "unconnected-(STM32F405RGT6-PC14-Pad3)") (class "Default")
      (node (ref "STM32F405RGT6") (pin "3") (pinfunction "PC14_3") (pintype "bidirectional"))
    )
    (net (code "68") (name "unconnected-(STM32F405RGT6-PC15-Pad4)") (class "Default")
      (node (ref "STM32F405RGT6") (pin "4") (pinfunction "PC15_4") (pintype "bidirectional"))
    )
    (net (code "69") (name "unconnected-(STM32F405RGT6-SPI1_MISO,SPI3_MISO,TIM3_CH1,PB4-Pad56)") (class "Default")
      (node (ref "STM32F405RGT6") (pin "56") (pinfunction "SPI1_MISO,SPI3_MISO,TIM3_CH1,PB4_56") (pintype "bidirectional"))
    )
    (net (code "70") (name "unconnected-(STM32F405RGT6-SPI1_MOSI,SPI3_MOSI,TIM3_CH2,CAN2_RX,PB5-Pad57)") (class "Default")
      (node (ref "STM32F405RGT6") (pin "57") (pinfunction "SPI1_MOSI,SPI3_MOSI,TIM3_CH2,CAN2_RX,PB5_57") (pintype "bidirectional"))
    )
    (net (code "71") (name "unconnected-(STM32F405RGT6-TIM1_CH1,I2C3_SCL,PA8-Pad41)") (class "Default")
      (node (ref "STM32F405RGT6") (pin "41") (pinfunction "TIM1_CH1,I2C3_SCL,PA8_41") (pintype "bidirectional"))
    )
    (net (code "72") (name "unconnected-(STM32F405RGT6-TIM3_CH1,TIM8_CH1,USART6_TX,SDIO_D6,PC6-Pad37)") (class "Default")
      (node (ref "STM32F405RGT6") (pin "37") (pinfunction "TIM3_CH1,TIM8_CH1,USART6_TX,SDIO_D6,PC6_37") (pintype "bidirectional"))
    )
    (net (code "73") (name "unconnected-(STM32F405RGT6-VBAT-Pad1)") (class "Default")
      (node (ref "STM32F405RGT6") (pin "1") (pinfunction "VBAT_1") (pintype "bidirectional"))
    )
    (net (code "74") (name "unconnected-(U$1-Pad3D-FIX)") (class "Default")
      (node (ref "U$1") (pin "3D-FIX") (pinfunction "3D-FIX_3D-FIX") (pintype "bidirectional"))
    )
    (net (code "75") (name "unconnected-(U$1-PadENABLE)") (class "Default")
      (node (ref "U$1") (pin "ENABLE") (pinfunction "ENABLE_ENABLE") (pintype "bidirectional"))
    )
    (net (code "76") (name "unconnected-(U$1-PadRX1)") (class "Default")
      (node (ref "U$1") (pin "RX1") (pinfunction "RX1_RX1") (pintype "bidirectional"))
    )
    (net (code "77") (name "unconnected-(U$1-PadTX1)") (class "Default")
      (node (ref "U$1") (pin "TX1") (pinfunction "TX1_TX1") (pintype "bidirectional"))
    )
    (net (code "78") (name "unconnected-(U$4-PadIS)") (class "Default")
      (node (ref "U$4") (pin "IS") (pinfunction "IS_IS") (pintype "bidirectional"))
    )
    (net (code "79") (name "unconnected-(U$11-PadIS)") (class "Default")
      (node (ref "U$11") (pin "IS") (pinfunction "IS_IS") (pintype "bidirectional"))
    )
  )
)
